# sample.net
KiCad netlist of a schematic drawn in EAGLE
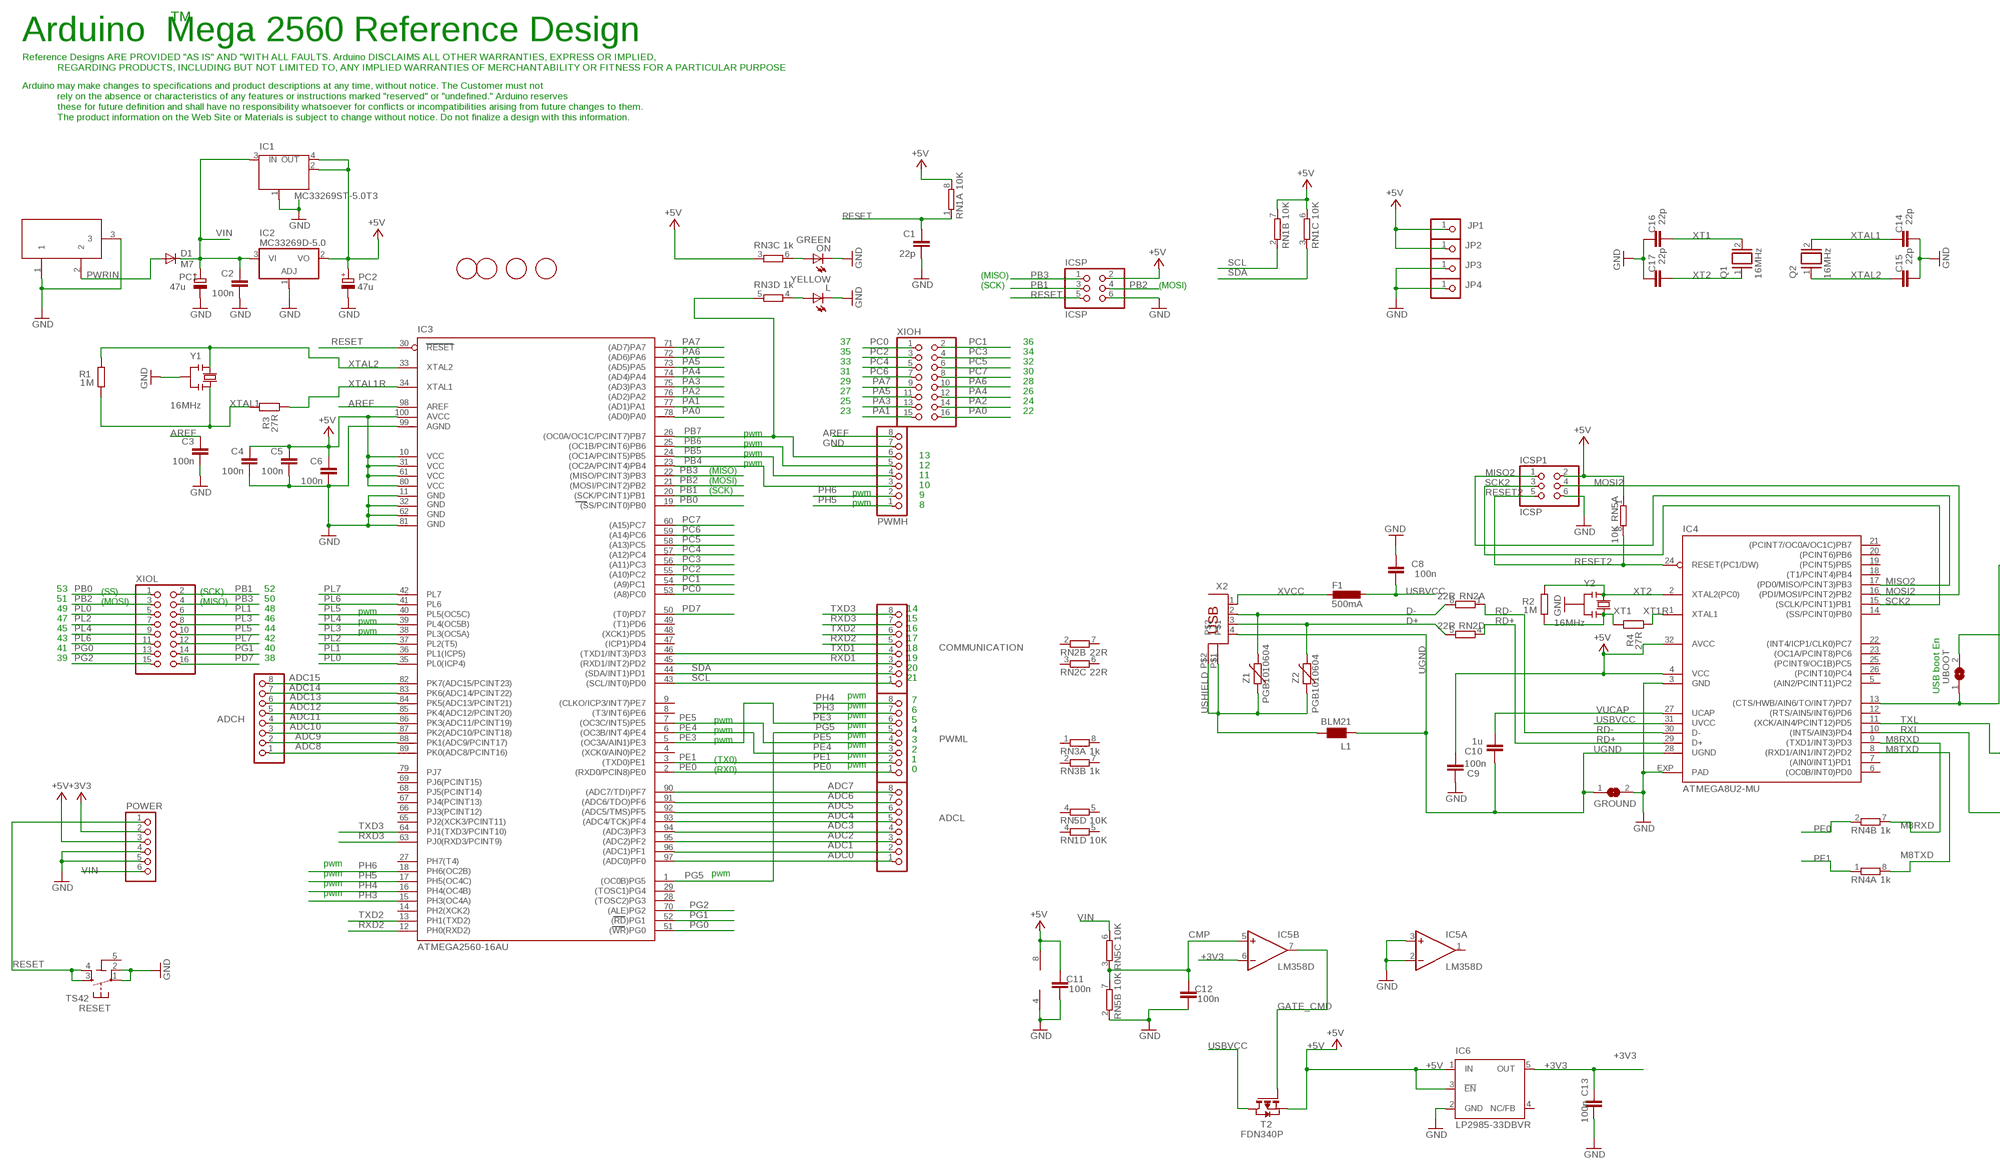
[diagram p0: schematic, sheet 1, part 1 of 2]
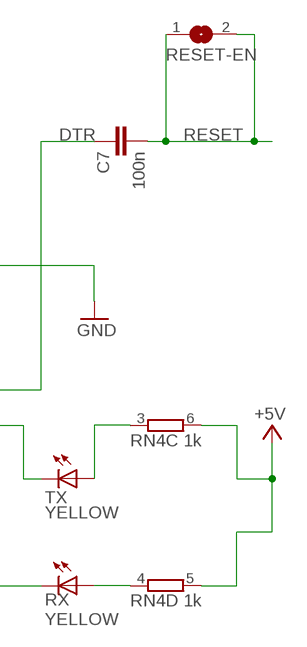
[diagram p1: schematic, sheet 1, part 2 of 2]

(export (version "E")
  (design (tool "Eeschema 10.0.6"))
  (components
    (comp (ref "ADCH")
      (value "PINHD-1X8")
      (footprint "eagle-import:1X08")
      (libsource (lib "eagle-import") (part "PINHD-1X8"))
    )
    (comp (ref "ADCL")
      (value "PINHD-1X8")
      (footprint "eagle-import:1X08")
      (libsource (lib "eagle-import") (part "PINHD-1X8"))
    )
    (comp (ref "C1")
      (value "22p")
      (footprint "eagle-import:C0603-ROUND")
      (libsource (lib "eagle-import") (part "C-EU0603-RND"))
    )
    (comp (ref "C2")
      (value "100n")
      (footprint "eagle-import:C0603-ROUND")
      (libsource (lib "eagle-import") (part "C-EU0603-RND"))
    )
    (comp (ref "C3")
      (value "100n")
      (footprint "eagle-import:C0603-ROUND")
      (libsource (lib "eagle-import") (part "C-EU0603-RND"))
    )
    (comp (ref "C4")
      (value "100n")
      (footprint "eagle-import:C0603-ROUND")
      (libsource (lib "eagle-import") (part "C-EU0603-RND"))
    )
    (comp (ref "C5")
      (value "100n")
      (footprint "eagle-import:C0603-ROUND")
      (libsource (lib "eagle-import") (part "C-EU0603-RND"))
    )
    (comp (ref "C6")
      (value "100n")
      (footprint "eagle-import:C0603-ROUND")
      (libsource (lib "eagle-import") (part "C-EU0603-RND"))
    )
    (comp (ref "C7")
      (value "100n")
      (footprint "eagle-import:C0603-ROUND")
      (libsource (lib "eagle-import") (part "C-EU0603-RND"))
    )
    (comp (ref "C8")
      (value "100n")
      (footprint "eagle-import:C0603")
      (libsource (lib "eagle-import") (part "rcl_C-EUC0603"))
    )
    (comp (ref "C9")
      (value "100n")
      (footprint "eagle-import:C0603-ROUND")
      (libsource (lib "eagle-import") (part "C-EU0603-RND"))
    )
    (comp (ref "C10")
      (value "1u")
      (footprint "eagle-import:C0603-ROUND")
      (libsource (lib "eagle-import") (part "C-EU0603-RND"))
    )
    (comp (ref "C11")
      (value "100n")
      (footprint "eagle-import:C0603")
      (libsource (lib "eagle-import") (part "rcl_C-EUC0603"))
    )
    (comp (ref "C12")
      (value "100n")
      (footprint "eagle-import:C0603-ROUND")
      (libsource (lib "eagle-import") (part "C-EU0603-RND"))
    )
    (comp (ref "C13")
      (value "100n")
      (footprint "eagle-import:C0603-ROUND")
      (libsource (lib "eagle-import") (part "C-EU0603-RND"))
    )
    (comp (ref "C14")
      (value "22p")
      (footprint "eagle-import:C0603-ROUND")
      (libsource (lib "eagle-import") (part "C-EU0603-RND"))
    )
    (comp (ref "C15")
      (value "22p")
      (footprint "eagle-import:C0603-ROUND")
      (libsource (lib "eagle-import") (part "C-EU0603-RND"))
    )
    (comp (ref "C16")
      (value "22p")
      (footprint "eagle-import:C0603-ROUND")
      (libsource (lib "eagle-import") (part "C-EU0603-RND"))
    )
    (comp (ref "C17")
      (value "22p")
      (footprint "eagle-import:C0603-ROUND")
      (libsource (lib "eagle-import") (part "C-EU0603-RND"))
    )
    (comp (ref "COMMUNICATION")
      (value "PINHD-1X8")
      (footprint "eagle-import:1X08")
      (libsource (lib "eagle-import") (part "PINHD-1X8"))
    )
    (comp (ref "D1")
      (value "M7")
      (footprint "eagle-import:SMB")
      (libsource (lib "eagle-import") (part "DIODE-SMB"))
    )
    (comp (ref "F1")
      (value "500mA")
      (footprint "eagle-import:L1812")
      (libsource (lib "eagle-import") (part "L-EUL1812"))
    )
    (comp (ref "GROUND")
      (value "SJ")
      (footprint "eagle-import:SJ")
      (libsource (lib "eagle-import") (part "SJ"))
    )
    (comp (ref "IC1")
      (value "MC33269ST-5.0T3")
      (footprint "eagle-import:SOT223")
      (libsource (lib "eagle-import") (part "MC33269ST-3.3T3"))
    )
    (comp (ref "IC2")
      (value "MC33269D-5.0")
      (footprint "eagle-import:DPACK")
      (libsource (lib "eagle-import") (part "MC33269?D-5.0"))
    )
    (comp (ref "IC3")
      (value "ATMEGA2560-16AU")
      (footprint "eagle-import:TQFP100")
      (libsource (lib "eagle-import") (part "ATMEGAAU1280-16"))
    )
    (comp (ref "IC4")
      (value "ATMEGA8U2-MU")
      (footprint "eagle-import:QFN32")
      (libsource (lib "eagle-import") (part "ATMEGA8U2-MU"))
    )
    (comp (ref "IC5")
      (value "LM358D")
      (footprint "eagle-import:SO08")
      (libsource (lib "eagle-import") (part "LM358D"))
    )
    (comp (ref "IC6")
      (value "LP2985-33DBVR")
      (footprint "eagle-import:SOT23-DBV")
      (libsource (lib "eagle-import") (part "TPS77033"))
    )
    (comp (ref "ICSP")
      (value "ICSP")
      (footprint "eagle-import:2X03")
      (libsource (lib "eagle-import") (part "PINHD-2X3"))
    )
    (comp (ref "ICSP1")
      (value "ICSP")
      (footprint "eagle-import:2X03")
      (libsource (lib "eagle-import") (part "PINHD-2X3"))
    )
    (comp (ref "JP1")
      (value "PINHD-1X1")
      (footprint "eagle-import:1X01")
      (libsource (lib "eagle-import") (part "PINHD-1X1"))
    )
    (comp (ref "JP2")
      (value "PINHD-1X1")
      (footprint "eagle-import:1X01")
      (libsource (lib "eagle-import") (part "PINHD-1X1"))
    )
    (comp (ref "JP3")
      (value "PINHD-1X1")
      (footprint "eagle-import:1X01")
      (libsource (lib "eagle-import") (part "PINHD-1X1"))
    )
    (comp (ref "JP4")
      (value "PINHD-1X1")
      (footprint "eagle-import:1X01")
      (libsource (lib "eagle-import") (part "PINHD-1X1"))
    )
    (comp (ref "L")
      (value "YELLOW")
      (footprint "eagle-import:CHIP-LED0805")
      (libsource (lib "eagle-import") (part "LEDCHIP-LED0805"))
    )
    (comp (ref "L1")
      (value "BLM21")
      (footprint "eagle-import:0805")
      (libsource (lib "eagle-import") (part "WE-CBF_0805"))
    )
    (comp (ref "ON")
      (value "GREEN")
      (footprint "eagle-import:CHIP-LED0805")
      (libsource (lib "eagle-import") (part "LEDCHIP-LED0805"))
    )
    (comp (ref "PC1")
      (value "47u")
      (footprint "eagle-import:PANASONIC_D")
      (libsource (lib "eagle-import") (part "CPOL-EUD"))
    )
    (comp (ref "PC2")
      (value "47u")
      (footprint "eagle-import:PANASONIC_D")
      (libsource (lib "eagle-import") (part "CPOL-EUD"))
    )
    (comp (ref "POWER")
      (value "PINHD-1X6")
      (footprint "eagle-import:1X06")
      (libsource (lib "eagle-import") (part "PINHD-1X6"))
    )
    (comp (ref "PWMH")
      (value "PINHD-1X8")
      (footprint "eagle-import:1X08")
      (libsource (lib "eagle-import") (part "PINHD-1X8"))
    )
    (comp (ref "PWML")
      (value "PINHD-1X8")
      (footprint "eagle-import:1X08")
      (libsource (lib "eagle-import") (part "PINHD-1X8"))
    )
    (comp (ref "Q1")
      (value "16MHz")
      (footprint "eagle-import:QS")
      (libsource (lib "eagle-import") (part "XTAL/S"))
    )
    (comp (ref "Q2")
      (value "16MHz")
      (footprint "eagle-import:QS")
      (libsource (lib "eagle-import") (part "XTAL/S"))
    )
    (comp (ref "R1")
      (value "1M")
      (footprint "eagle-import:R0603-ROUND")
      (libsource (lib "eagle-import") (part "R-EU_R0603"))
    )
    (comp (ref "R2")
      (value "1M")
      (footprint "eagle-import:R0603-ROUND")
      (libsource (lib "eagle-import") (part "R-EU_R0603"))
    )
    (comp (ref "R3")
      (value "27R")
      (footprint "eagle-import:R0603-ROUND")
      (libsource (lib "eagle-import") (part "R-EU_R0603"))
    )
    (comp (ref "R4")
      (value "27R")
      (footprint "eagle-import:R0603-ROUND")
      (libsource (lib "eagle-import") (part "R-EU_R0603"))
    )
    (comp (ref "RESET")
      (value "TS42")
      (footprint "eagle-import:TS42")
      (libsource (lib "eagle-import") (part "TS42"))
    )
    (comp (ref "RESET-EN")
      (value "SJ")
      (footprint "eagle-import:SJ")
      (libsource (lib "eagle-import") (part "SJ"))
    )
    (comp (ref "RN1")
      (value "10K")
      (footprint "eagle-import:CAT16")
      (libsource (lib "eagle-import") (part "4R-NCAT16"))
    )
    (comp (ref "RN2")
      (value "22R")
      (footprint "eagle-import:CAY16")
      (libsource (lib "eagle-import") (part "4R-NCAY16"))
    )
    (comp (ref "RN3")
      (value "1k")
      (footprint "eagle-import:CAY16")
      (libsource (lib "eagle-import") (part "4R-NCAY16"))
    )
    (comp (ref "RN4")
      (value "1k")
      (footprint "eagle-import:CAY16")
      (libsource (lib "eagle-import") (part "4R-NCAY16"))
    )
    (comp (ref "RN5")
      (value "10K")
      (footprint "eagle-import:CAT16")
      (libsource (lib "eagle-import") (part "4R-NCAT16"))
    )
    (comp (ref "RX")
      (value "YELLOW")
      (footprint "eagle-import:CHIP-LED0805")
      (libsource (lib "eagle-import") (part "LEDCHIP-LED0805"))
    )
    (comp (ref "T2")
      (value "FDN340P")
      (footprint "eagle-import:SOT-23")
      (libsource (lib "eagle-import") (part "PMOSSOT23"))
    )
    (comp (ref "TX")
      (value "YELLOW")
      (footprint "eagle-import:CHIP-LED0805")
      (libsource (lib "eagle-import") (part "LEDCHIP-LED0805"))
    )
    (comp (ref "U$2")
      (value "FIDUCIALMOUNT")
      (footprint "eagle-import:FIDUCIA-MOUNT")
      (libsource (lib "eagle-import") (part "FIDUCIALMOUNT"))
    )
    (comp (ref "U$3")
      (value "FIDUCIALMOUNT")
      (footprint "eagle-import:FIDUCIA-MOUNT")
      (libsource (lib "eagle-import") (part "FIDUCIALMOUNT"))
    )
    (comp (ref "U$4")
      (value "FIDUCIALMOUNT")
      (footprint "eagle-import:FIDUCIA-MOUNT")
      (libsource (lib "eagle-import") (part "FIDUCIALMOUNT"))
    )
    (comp (ref "U$5")
      (value "FIDUCIALMOUNT")
      (footprint "eagle-import:FIDUCIA-MOUNT")
      (libsource (lib "eagle-import") (part "FIDUCIALMOUNT"))
    )
    (comp (ref "UBOOT")
      (value "SJ")
      (footprint "eagle-import:SJ")
      (libsource (lib "eagle-import") (part "SJ"))
    )
    (comp (ref "X1")
      (value "DC21MMX")
      (footprint "eagle-import:DC-21MM")
      (libsource (lib "eagle-import") (part "DC21MMX"))
    )
    (comp (ref "X2")
      (value "PN61729")
      (footprint "eagle-import:PN61729")
      (libsource (lib "eagle-import") (part "PN61729"))
    )
    (comp (ref "XIOH")
      (value "PINHD-2X8")
      (footprint "eagle-import:2X08")
      (libsource (lib "eagle-import") (part "PINHD-2X8"))
    )
    (comp (ref "XIOL")
      (value "PINHD-2X8")
      (footprint "eagle-import:2X08")
      (libsource (lib "eagle-import") (part "PINHD-2X8"))
    )
    (comp (ref "Y1")
      (value "16MHz")
      (footprint "eagle-import:RESONATOR")
      (libsource (lib "eagle-import") (part "RESONATORMU"))
    )
    (comp (ref "Y2")
      (value "16MHz")
      (footprint "eagle-import:RESONATOR")
      (libsource (lib "eagle-import") (part "RESONATORMU"))
    )
    (comp (ref "Z1")
      (value "PGB1010604")
      (footprint "eagle-import:CT_CN0603")
      (libsource (lib "eagle-import") (part "VARISTORCN0603"))
    )
    (comp (ref "Z2")
      (value "PGB1010604")
      (footprint "eagle-import:CT_CN0603")
      (libsource (lib "eagle-import") (part "VARISTORCN0603"))
    )
  )
  (nets
    (net (code "1") (name "+3V3") (class "Default")
      (node (ref "C13") (pin "2") (pinfunction "2_2") (pintype "passive"))
      (node (ref "IC5") (pin "6") (pinfunction "-IN_6") (pintype "input"))
      (node (ref "IC6") (pin "5") (pinfunction "OUT_5") (pintype "passive"))
      (node (ref "POWER") (pin "2") (pinfunction "2_2") (pintype "passive"))
    )
    (net (code "2") (name "+5V") (class "Default")
      (node (ref "C11") (pin "2") (pinfunction "2_2") (pintype "passive"))
      (node (ref "C4") (pin "1") (pinfunction "1_1") (pintype "passive"))
      (node (ref "C5") (pin "1") (pinfunction "1_1") (pintype "passive"))
      (node (ref "C6") (pin "1") (pinfunction "1_1") (pintype "passive"))
      (node (ref "C9") (pin "1") (pinfunction "1_1") (pintype "passive"))
      (node (ref "IC1") (pin "2") (pinfunction "OUT_2") (pintype "passive"))
      (node (ref "IC1") (pin "4") (pinfunction "OUT_4") (pintype "passive"))
      (node (ref "IC2") (pin "2") (pinfunction "VO_2") (pintype "passive"))
      (node (ref "IC3") (pin "10") (pinfunction "VCC_10") (pintype "power_in"))
      (node (ref "IC3") (pin "100") (pinfunction "AVCC_100") (pintype "power_in"))
      (node (ref "IC3") (pin "31") (pinfunction "VCC1_31") (pintype "power_in"))
      (node (ref "IC3") (pin "61") (pinfunction "VCC2_61") (pintype "power_in"))
      (node (ref "IC3") (pin "80") (pinfunction "VCC3_80") (pintype "power_in"))
      (node (ref "IC4") (pin "32") (pinfunction "AVCC_32") (pintype "power_in"))
      (node (ref "IC4") (pin "4") (pinfunction "VCC_4") (pintype "power_in"))
      (node (ref "IC5") (pin "8") (pinfunction "V+_8") (pintype "power_in"))
      (node (ref "IC6") (pin "1") (pinfunction "IN_1") (pintype "input"))
      (node (ref "IC6") (pin "3") (pinfunction "~{EN}_3") (pintype "input"))
      (node (ref "ICSP") (pin "2") (pinfunction "2_2") (pintype "passive"))
      (node (ref "ICSP1") (pin "2") (pinfunction "2_2") (pintype "passive"))
      (node (ref "JP1") (pin "1") (pinfunction "1_1") (pintype "passive"))
      (node (ref "JP2") (pin "1") (pinfunction "1_1") (pintype "passive"))
      (node (ref "PC2") (pin "+") (pinfunction "+_+") (pintype "passive"))
      (node (ref "POWER") (pin "3") (pinfunction "3_3") (pintype "passive"))
      (node (ref "RN1") (pin "6") (pinfunction "2_6") (pintype "passive"))
      (node (ref "RN1") (pin "7") (pinfunction "2_7") (pintype "passive"))
      (node (ref "RN1") (pin "8") (pinfunction "2_8") (pintype "passive"))
      (node (ref "RN3") (pin "3") (pinfunction "1_3") (pintype "passive"))
      (node (ref "RN4") (pin "5") (pinfunction "2_5") (pintype "passive"))
      (node (ref "RN4") (pin "6") (pinfunction "2_6") (pintype "passive"))
      (node (ref "RN5") (pin "1") (pinfunction "1_1") (pintype "passive"))
      (node (ref "T2") (pin "2") (pinfunction "S_2") (pintype "passive"))
    )
    (net (code "3") (name "/5-GND") (class "Default")
      (node (ref "RESET") (pin "5") (pinfunction "5-GND_5") (pintype "power_in"))
    )
    (net (code "4") (name "/ADC0") (class "Default")
      (node (ref "ADCL") (pin "1") (pinfunction "1_1") (pintype "passive"))
      (node (ref "IC3") (pin "97") (pinfunction "(ADC0)PF0_97") (pintype "bidirectional"))
    )
    (net (code "5") (name "/ADC1") (class "Default")
      (node (ref "ADCL") (pin "2") (pinfunction "2_2") (pintype "passive"))
      (node (ref "IC3") (pin "96") (pinfunction "(ADC1)PF1_96") (pintype "bidirectional"))
    )
    (net (code "6") (name "/ADC2") (class "Default")
      (node (ref "ADCL") (pin "3") (pinfunction "3_3") (pintype "passive"))
      (node (ref "IC3") (pin "95") (pinfunction "(ADC2)PF2_95") (pintype "bidirectional"))
    )
    (net (code "7") (name "/ADC3") (class "Default")
      (node (ref "ADCL") (pin "4") (pinfunction "4_4") (pintype "passive"))
      (node (ref "IC3") (pin "94") (pinfunction "(ADC3)PF3_94") (pintype "bidirectional"))
    )
    (net (code "8") (name "/ADC4") (class "Default")
      (node (ref "ADCL") (pin "5") (pinfunction "5_5") (pintype "passive"))
      (node (ref "IC3") (pin "93") (pinfunction "(ADC4/TCK)PF4_93") (pintype "bidirectional"))
    )
    (net (code "9") (name "/ADC5") (class "Default")
      (node (ref "ADCL") (pin "6") (pinfunction "6_6") (pintype "passive"))
      (node (ref "IC3") (pin "92") (pinfunction "(ADC5/TMS)PF5_92") (pintype "bidirectional"))
    )
    (net (code "10") (name "/ADC6") (class "Default")
      (node (ref "ADCL") (pin "7") (pinfunction "7_7") (pintype "passive"))
      (node (ref "IC3") (pin "91") (pinfunction "(ADC6/TDO)PF6_91") (pintype "bidirectional"))
    )
    (net (code "11") (name "/ADC7") (class "Default")
      (node (ref "ADCL") (pin "8") (pinfunction "8_8") (pintype "passive"))
      (node (ref "IC3") (pin "90") (pinfunction "(ADC7/TDI)PF7_90") (pintype "bidirectional"))
    )
    (net (code "12") (name "/ADC8") (class "Default")
      (node (ref "ADCH") (pin "1") (pinfunction "1_1") (pintype "passive"))
      (node (ref "IC3") (pin "89") (pinfunction "PK0(ADC8/PCINT16)_89") (pintype "bidirectional"))
    )
    (net (code "13") (name "/ADC9") (class "Default")
      (node (ref "ADCH") (pin "2") (pinfunction "2_2") (pintype "passive"))
      (node (ref "IC3") (pin "88") (pinfunction "PK1(ADC9/PCINT17)_88") (pintype "bidirectional"))
    )
    (net (code "14") (name "/ADC10") (class "Default")
      (node (ref "ADCH") (pin "3") (pinfunction "3_3") (pintype "passive"))
      (node (ref "IC3") (pin "87") (pinfunction "PK2(ADC10/PCINT18)_87") (pintype "bidirectional"))
    )
    (net (code "15") (name "/ADC11") (class "Default")
      (node (ref "ADCH") (pin "4") (pinfunction "4_4") (pintype "passive"))
      (node (ref "IC3") (pin "86") (pinfunction "PK3(ADC11/PCINT19)_86") (pintype "bidirectional"))
    )
    (net (code "16") (name "/ADC12") (class "Default")
      (node (ref "ADCH") (pin "5") (pinfunction "5_5") (pintype "passive"))
      (node (ref "IC3") (pin "85") (pinfunction "PK4(ADC12/PCINT20)_85") (pintype "bidirectional"))
    )
    (net (code "17") (name "/ADC13") (class "Default")
      (node (ref "ADCH") (pin "6") (pinfunction "6_6") (pintype "passive"))
      (node (ref "IC3") (pin "84") (pinfunction "PK5(ADC13/PCINT21)_84") (pintype "bidirectional"))
    )
    (net (code "18") (name "/ADC14") (class "Default")
      (node (ref "ADCH") (pin "7") (pinfunction "7_7") (pintype "passive"))
      (node (ref "IC3") (pin "83") (pinfunction "PK6(ADC14/PCINT22)_83") (pintype "bidirectional"))
    )
    (net (code "19") (name "/ADC15") (class "Default")
      (node (ref "ADCH") (pin "8") (pinfunction "8_8") (pintype "passive"))
      (node (ref "IC3") (pin "82") (pinfunction "PK7(ADC15/PCINT23)_82") (pintype "bidirectional"))
    )
    (net (code "20") (name "/AREF") (class "Default")
      (node (ref "C3") (pin "1") (pinfunction "1_1") (pintype "passive"))
      (node (ref "IC3") (pin "98") (pinfunction "AREF_98") (pintype "bidirectional"))
      (node (ref "PWMH") (pin "8") (pinfunction "8_8") (pintype "passive"))
    )
    (net (code "21") (name "/CMP") (class "Default")
      (node (ref "C12") (pin "2") (pinfunction "2_2") (pintype "passive"))
      (node (ref "IC5") (pin "5") (pinfunction "+IN_5") (pintype "input"))
      (node (ref "RN5") (pin "3") (pinfunction "1_3") (pintype "passive"))
      (node (ref "RN5") (pin "7") (pinfunction "2_7") (pintype "passive"))
    )
    (net (code "22") (name "/D+") (class "Default")
      (node (ref "RN2") (pin "5") (pinfunction "2_5") (pintype "passive"))
      (node (ref "X2") (pin "3") (pinfunction "3_3") (pintype "bidirectional"))
      (node (ref "Z2") (pin "2") (pinfunction "2_2") (pintype "passive"))
    )
    (net (code "23") (name "/D-") (class "Default")
      (node (ref "RN2") (pin "8") (pinfunction "2_8") (pintype "passive"))
      (node (ref "X2") (pin "2") (pinfunction "2_2") (pintype "bidirectional"))
      (node (ref "Z1") (pin "2") (pinfunction "2_2") (pintype "passive"))
    )
    (net (code "24") (name "/DTR") (class "Default")
      (node (ref "C7") (pin "1") (pinfunction "1_1") (pintype "passive"))
      (node (ref "IC4") (pin "13") (pinfunction "(CTS/HWB/AIN6/TO/INT7)PD7_13") (pintype "bidirectional"))
      (node (ref "UBOOT") (pin "1") (pinfunction "1_1") (pintype "passive"))
    )
    (net (code "25") (name "/GATE_CMD") (class "Default")
      (node (ref "IC5") (pin "7") (pinfunction "OUT_7") (pintype "output"))
      (node (ref "T2") (pin "3") (pinfunction "G_3") (pintype "passive"))
    )
    (net (code "26") (name "/M8RXD") (class "Default")
      (node (ref "IC4") (pin "9") (pinfunction "(TXD1/INT3)PD3_9") (pintype "bidirectional"))
      (node (ref "RN4") (pin "7") (pinfunction "2_7") (pintype "passive"))
    )
    (net (code "27") (name "/M8TXD") (class "Default")
      (node (ref "IC4") (pin "8") (pinfunction "(RXD1/AIN1/INT2)PD2_8") (pintype "bidirectional"))
      (node (ref "RN4") (pin "8") (pinfunction "2_8") (pintype "passive"))
    )
    (net (code "28") (name "/MISO2") (class "Default")
      (node (ref "IC4") (pin "17") (pinfunction "(PD0/MISO/PCINT3)PB3_17") (pintype "bidirectional"))
      (node (ref "ICSP1") (pin "1") (pinfunction "1_1") (pintype "passive"))
    )
    (net (code "29") (name "/MOSI2") (class "Default")
      (node (ref "IC4") (pin "16") (pinfunction "(PDI/MOSI/PCINT2)PB2_16") (pintype "bidirectional"))
      (node (ref "ICSP1") (pin "4") (pinfunction "4_4") (pintype "passive"))
    )
    (net (code "30") (name "/PA0") (class "Default")
      (node (ref "IC3") (pin "78") (pinfunction "(AD0)PA0_78") (pintype "bidirectional"))
      (node (ref "XIOH") (pin "16") (pinfunction "16_16") (pintype "passive"))
    )
    (net (code "31") (name "/PA1") (class "Default")
      (node (ref "IC3") (pin "77") (pinfunction "(AD1)PA1_77") (pintype "bidirectional"))
      (node (ref "XIOH") (pin "15") (pinfunction "15_15") (pintype "passive"))
    )
    (net (code "32") (name "/PA2") (class "Default")
      (node (ref "IC3") (pin "76") (pinfunction "(AD2)PA2_76") (pintype "bidirectional"))
      (node (ref "XIOH") (pin "14") (pinfunction "14_14") (pintype "passive"))
    )
    (net (code "33") (name "/PA3") (class "Default")
      (node (ref "IC3") (pin "75") (pinfunction "(AD3)PA3_75") (pintype "bidirectional"))
      (node (ref "XIOH") (pin "13") (pinfunction "13_13") (pintype "passive"))
    )
    (net (code "34") (name "/PA4") (class "Default")
      (node (ref "IC3") (pin "74") (pinfunction "(AD4)PA4_74") (pintype "bidirectional"))
      (node (ref "XIOH") (pin "12") (pinfunction "12_12") (pintype "passive"))
    )
    (net (code "35") (name "/PA5") (class "Default")
      (node (ref "IC3") (pin "73") (pinfunction "(AD5)PA5_73") (pintype "bidirectional"))
      (node (ref "XIOH") (pin "11") (pinfunction "11_11") (pintype "passive"))
    )
    (net (code "36") (name "/PA6") (class "Default")
      (node (ref "IC3") (pin "72") (pinfunction "(AD6)PA6_72") (pintype "bidirectional"))
      (node (ref "XIOH") (pin "10") (pinfunction "10_10") (pintype "passive"))
    )
    (net (code "37") (name "/PA7") (class "Default")
      (node (ref "IC3") (pin "71") (pinfunction "(AD7)PA7_71") (pintype "bidirectional"))
      (node (ref "XIOH") (pin "9") (pinfunction "9_9") (pintype "passive"))
    )
    (net (code "38") (name "/PB0") (class "Default")
      (node (ref "IC3") (pin "19") (pinfunction "(SS/PCINT0)PB0_19") (pintype "bidirectional"))
      (node (ref "XIOL") (pin "1") (pinfunction "1_1") (pintype "passive"))
    )
    (net (code "39") (name "/PB1") (class "Default")
      (node (ref "IC3") (pin "20") (pinfunction "(SCK/PCINT1)PB1_20") (pintype "bidirectional"))
      (node (ref "ICSP") (pin "3") (pinfunction "3_3") (pintype "passive"))
      (node (ref "XIOL") (pin "2") (pinfunction "2_2") (pintype "passive"))
    )
    (net (code "40") (name "/PB2") (class "Default")
      (node (ref "IC3") (pin "21") (pinfunction "(MOSI/PCINT2)PB2_21") (pintype "bidirectional"))
      (node (ref "ICSP") (pin "4") (pinfunction "4_4") (pintype "passive"))
      (node (ref "XIOL") (pin "3") (pinfunction "3_3") (pintype "passive"))
    )
    (net (code "41") (name "/PB3") (class "Default")
      (node (ref "IC3") (pin "22") (pinfunction "(MISO/PCINT3)PB3_22") (pintype "bidirectional"))
      (node (ref "ICSP") (pin "1") (pinfunction "1_1") (pintype "passive"))
      (node (ref "XIOL") (pin "4") (pinfunction "4_4") (pintype "passive"))
    )
    (net (code "42") (name "/PB4") (class "Default")
      (node (ref "IC3") (pin "23") (pinfunction "(OC2A/PCINT4)PB4_23") (pintype "bidirectional"))
      (node (ref "PWMH") (pin "3") (pinfunction "3_3") (pintype "passive"))
    )
    (net (code "43") (name "/PB5") (class "Default")
      (node (ref "IC3") (pin "24") (pinfunction "(OC1A/PCINT5)PB5_24") (pintype "bidirectional"))
      (node (ref "PWMH") (pin "4") (pinfunction "4_4") (pintype "passive"))
    )
    (net (code "44") (name "/PB6") (class "Default")
      (node (ref "IC3") (pin "25") (pinfunction "(OC1B/PCINT6)PB6_25") (pintype "bidirectional"))
      (node (ref "PWMH") (pin "5") (pinfunction "5_5") (pintype "passive"))
    )
    (net (code "45") (name "/PB7") (class "Default")
      (node (ref "IC3") (pin "26") (pinfunction "(OC0A/OC1C/PCINT7)PB7_26") (pintype "bidirectional"))
      (node (ref "PWMH") (pin "6") (pinfunction "6_6") (pintype "passive"))
      (node (ref "RN3") (pin "5") (pinfunction "2_5") (pintype "passive"))
    )
    (net (code "46") (name "/PC0") (class "Default")
      (node (ref "IC3") (pin "53") (pinfunction "(A8)PC0_53") (pintype "bidirectional"))
      (node (ref "XIOH") (pin "1") (pinfunction "1_1") (pintype "passive"))
    )
    (net (code "47") (name "/PC1") (class "Default")
      (node (ref "IC3") (pin "54") (pinfunction "(A9)PC1_54") (pintype "bidirectional"))
      (node (ref "XIOH") (pin "2") (pinfunction "2_2") (pintype "passive"))
    )
    (net (code "48") (name "/PC2") (class "Default")
      (node (ref "IC3") (pin "55") (pinfunction "(A10)PC2_55") (pintype "bidirectional"))
      (node (ref "XIOH") (pin "3") (pinfunction "3_3") (pintype "passive"))
    )
    (net (code "49") (name "/PC3") (class "Default")
      (node (ref "IC3") (pin "56") (pinfunction "(A11)PC3_56") (pintype "bidirectional"))
      (node (ref "XIOH") (pin "4") (pinfunction "4_4") (pintype "passive"))
    )
    (net (code "50") (name "/PC4") (class "Default")
      (node (ref "IC3") (pin "57") (pinfunction "(A12)PC4_57") (pintype "bidirectional"))
      (node (ref "XIOH") (pin "5") (pinfunction "5_5") (pintype "passive"))
    )
    (net (code "51") (name "/PC5") (class "Default")
      (node (ref "IC3") (pin "58") (pinfunction "(A13)PC5_58") (pintype "bidirectional"))
      (node (ref "XIOH") (pin "6") (pinfunction "6_6") (pintype "passive"))
    )
    (net (code "52") (name "/PC6") (class "Default")
      (node (ref "IC3") (pin "59") (pinfunction "(A14)PC6_59") (pintype "bidirectional"))
      (node (ref "XIOH") (pin "7") (pinfunction "7_7") (pintype "passive"))
    )
    (net (code "53") (name "/PC7") (class "Default")
      (node (ref "IC3") (pin "60") (pinfunction "(A15)PC7_60") (pintype "bidirectional"))
      (node (ref "XIOH") (pin "8") (pinfunction "8_8") (pintype "passive"))
    )
    (net (code "54") (name "/PD7") (class "Default")
      (node (ref "IC3") (pin "50") (pinfunction "(T0)PD7_50") (pintype "bidirectional"))
      (node (ref "XIOL") (pin "16") (pinfunction "16_16") (pintype "passive"))
    )
    (net (code "55") (name "/PE0") (class "Default")
      (node (ref "IC3") (pin "2") (pinfunction "(RXD0/PCIN8)PE0_2") (pintype "bidirectional"))
      (node (ref "PWML") (pin "1") (pinfunction "1_1") (pintype "passive"))
      (node (ref "RN4") (pin "2") (pinfunction "1_2") (pintype "passive"))
    )
    (net (code "56") (name "/PE1") (class "Default")
      (node (ref "IC3") (pin "3") (pinfunction "(TXD0)PE1_3") (pintype "bidirectional"))
      (node (ref "PWML") (pin "2") (pinfunction "2_2") (pintype "passive"))
      (node (ref "RN4") (pin "1") (pinfunction "1_1") (pintype "passive"))
    )
    (net (code "57") (name "/PE3") (class "Default")
      (node (ref "IC3") (pin "5") (pinfunction "(OC3A/AIN1)PE3_5") (pintype "bidirectional"))
      (node (ref "PWML") (pin "6") (pinfunction "6_6") (pintype "passive"))
    )
    (net (code "58") (name "/PE4") (class "Default")
      (node (ref "IC3") (pin "6") (pinfunction "(OC3B/INT4)PE4_6") (pintype "bidirectional"))
      (node (ref "PWML") (pin "3") (pinfunction "3_3") (pintype "passive"))
    )
    (net (code "59") (name "/PE5") (class "Default")
      (node (ref "IC3") (pin "7") (pinfunction "(OC3C/INT5)PE5_7") (pintype "bidirectional"))
      (node (ref "PWML") (pin "4") (pinfunction "4_4") (pintype "passive"))
    )
    (net (code "60") (name "/PG0") (class "Default")
      (node (ref "IC3") (pin "51") (pinfunction "(WR)PG0_51") (pintype "bidirectional"))
      (node (ref "XIOL") (pin "13") (pinfunction "13_13") (pintype "passive"))
    )
    (net (code "61") (name "/PG1") (class "Default")
      (node (ref "IC3") (pin "52") (pinfunction "(RD)PG1_52") (pintype "bidirectional"))
      (node (ref "XIOL") (pin "14") (pinfunction "14_14") (pintype "passive"))
    )
    (net (code "62") (name "/PG2") (class "Default")
      (node (ref "IC3") (pin "70") (pinfunction "(ALE)PG2_70") (pintype "bidirectional"))
      (node (ref "XIOL") (pin "15") (pinfunction "15_15") (pintype "passive"))
    )
    (net (code "63") (name "/PG5") (class "Default")
      (node (ref "IC3") (pin "1") (pinfunction "(OC0B)PG5_1") (pintype "bidirectional"))
      (node (ref "PWML") (pin "5") (pinfunction "5_5") (pintype "passive"))
    )
    (net (code "64") (name "/PH3") (class "Default")
      (node (ref "IC3") (pin "15") (pinfunction "PH3(OC4A)_15") (pintype "bidirectional"))
      (node (ref "PWML") (pin "7") (pinfunction "7_7") (pintype "passive"))
    )
    (net (code "65") (name "/PH4") (class "Default")
      (node (ref "IC3") (pin "16") (pinfunction "PH4(OC4B)_16") (pintype "bidirectional"))
      (node (ref "PWML") (pin "8") (pinfunction "8_8") (pintype "passive"))
    )
    (net (code "66") (name "/PH5") (class "Default")
      (node (ref "IC3") (pin "17") (pinfunction "PH5(OC4C)_17") (pintype "bidirectional"))
      (node (ref "PWMH") (pin "1") (pinfunction "1_1") (pintype "passive"))
    )
    (net (code "67") (name "/PH6") (class "Default")
      (node (ref "IC3") (pin "18") (pinfunction "PH6(OC2B)_18") (pintype "bidirectional"))
      (node (ref "PWMH") (pin "2") (pinfunction "2_2") (pintype "passive"))
    )
    (net (code "68") (name "/PL0") (class "Default")
      (node (ref "IC3") (pin "35") (pinfunction "PL0(ICP4)_35") (pintype "bidirectional"))
      (node (ref "XIOL") (pin "5") (pinfunction "5_5") (pintype "passive"))
    )
    (net (code "69") (name "/PL1") (class "Default")
      (node (ref "IC3") (pin "36") (pinfunction "PL1(ICP5)_36") (pintype "bidirectional"))
      (node (ref "XIOL") (pin "6") (pinfunction "6_6") (pintype "passive"))
    )
    (net (code "70") (name "/PL2") (class "Default")
      (node (ref "IC3") (pin "37") (pinfunction "PL2(T5)_37") (pintype "bidirectional"))
      (node (ref "XIOL") (pin "7") (pinfunction "7_7") (pintype "passive"))
    )
    (net (code "71") (name "/PL3") (class "Default")
      (node (ref "IC3") (pin "38") (pinfunction "PL3(OC5A)_38") (pintype "bidirectional"))
      (node (ref "XIOL") (pin "8") (pinfunction "8_8") (pintype "passive"))
    )
    (net (code "72") (name "/PL4") (class "Default")
      (node (ref "IC3") (pin "39") (pinfunction "PL4(OC5B)_39") (pintype "bidirectional"))
      (node (ref "XIOL") (pin "9") (pinfunction "9_9") (pintype "passive"))
    )
    (net (code "73") (name "/PL5") (class "Default")
      (node (ref "IC3") (pin "40") (pinfunction "PL5(OC5C)_40") (pintype "bidirectional"))
      (node (ref "XIOL") (pin "10") (pinfunction "10_10") (pintype "passive"))
    )
    (net (code "74") (name "/PL6") (class "Default")
      (node (ref "IC3") (pin "41") (pinfunction "PL6_41") (pintype "bidirectional"))
      (node (ref "XIOL") (pin "11") (pinfunction "11_11") (pintype "passive"))
    )
    (net (code "75") (name "/PL7") (class "Default")
      (node (ref "IC3") (pin "42") (pinfunction "PL7_42") (pintype "bidirectional"))
      (node (ref "XIOL") (pin "12") (pinfunction "12_12") (pintype "passive"))
    )
    (net (code "76") (name "/PWRIN") (class "Default")
      (node (ref "D1") (pin "A") (pinfunction "A_A") (pintype "passive"))
      (node (ref "X1") (pin "2") (pinfunction "2_2") (pintype "power_in"))
    )
    (net (code "77") (name "/RD+") (class "Default")
      (node (ref "IC4") (pin "29") (pinfunction "D+_29") (pintype "bidirectional"))
      (node (ref "RN2") (pin "4") (pinfunction "1_4") (pintype "passive"))
    )
    (net (code "78") (name "/RD-") (class "Default")
      (node (ref "IC4") (pin "30") (pinfunction "D-_30") (pintype "bidirectional"))
      (node (ref "RN2") (pin "1") (pinfunction "1_1") (pintype "passive"))
    )
    (net (code "79") (name "/RESET") (class "Default")
      (node (ref "C1") (pin "1") (pinfunction "1_1") (pintype "passive"))
      (node (ref "C7") (pin "2") (pinfunction "2_2") (pintype "passive"))
      (node (ref "IC3") (pin "30") (pinfunction "RESET_30") (pintype "input"))
      (node (ref "ICSP") (pin "5") (pinfunction "5_5") (pintype "passive"))
      (node (ref "POWER") (pin "1") (pinfunction "1_1") (pintype "passive"))
      (node (ref "RESET") (pin "3") (pinfunction "3_3") (pintype "passive"))
      (node (ref "RESET") (pin "4") (pinfunction "4_4") (pintype "passive"))
      (node (ref "RESET-EN") (pin "1") (pinfunction "1_1") (pintype "passive"))
      (node (ref "RESET-EN") (pin "2") (pinfunction "2_2") (pintype "passive"))
      (node (ref "RN1") (pin "1") (pinfunction "1_1") (pintype "passive"))
    )
    (net (code "80") (name "/RESET2") (class "Default")
      (node (ref "IC4") (pin "24") (pinfunction "RESET(PC1/DW)_24") (pintype "input"))
      (node (ref "ICSP1") (pin "5") (pinfunction "5_5") (pintype "passive"))
      (node (ref "RN5") (pin "8") (pinfunction "2_8") (pintype "passive"))
    )
    (net (code "81") (name "/RXD1") (class "Default")
      (node (ref "COMMUNICATION") (pin "3") (pinfunction "3_3") (pintype "passive"))
      (node (ref "IC3") (pin "45") (pinfunction "(RXD1/INT2)PD2_45") (pintype "bidirectional"))
    )
    (net (code "82") (name "/RXD2") (class "Default")
      (node (ref "COMMUNICATION") (pin "5") (pinfunction "5_5") (pintype "passive"))
      (node (ref "IC3") (pin "12") (pinfunction "PH0(RXD2)_12") (pintype "bidirectional"))
    )
    (net (code "83") (name "/RXD3") (class "Default")
      (node (ref "COMMUNICATION") (pin "7") (pinfunction "7_7") (pintype "passive"))
      (node (ref "IC3") (pin "63") (pinfunction "PJ0(RXD3/PCINT9)_63") (pintype "bidirectional"))
    )
    (net (code "84") (name "/RXL") (class "Default")
      (node (ref "IC4") (pin "10") (pinfunction "(INT5/AIN3)PD4_10") (pintype "bidirectional"))
      (node (ref "RX") (pin "C") (pinfunction "C_C") (pintype "passive"))
    )
    (net (code "85") (name "/SCK2") (class "Default")
      (node (ref "IC4") (pin "15") (pinfunction "(SCLK/PCINT1)PB1_15") (pintype "bidirectional"))
      (node (ref "ICSP1") (pin "3") (pinfunction "3_3") (pintype "passive"))
    )
    (net (code "86") (name "/SCL") (class "Default")
      (node (ref "COMMUNICATION") (pin "1") (pinfunction "1_1") (pintype "passive"))
      (node (ref "IC3") (pin "43") (pinfunction "(SCL/INT0)PD0_43") (pintype "bidirectional"))
      (node (ref "RN1") (pin "2") (pinfunction "1_2") (pintype "passive"))
    )
    (net (code "87") (name "/SDA") (class "Default")
      (node (ref "COMMUNICATION") (pin "2") (pinfunction "2_2") (pintype "passive"))
      (node (ref "IC3") (pin "44") (pinfunction "(SDA/INT1)PD1_44") (pintype "bidirectional"))
      (node (ref "RN1") (pin "3") (pinfunction "1_3") (pintype "passive"))
    )
    (net (code "88") (name "/TXD1") (class "Default")
      (node (ref "COMMUNICATION") (pin "4") (pinfunction "4_4") (pintype "passive"))
      (node (ref "IC3") (pin "46") (pinfunction "(TXD1/INT3)PD3_46") (pintype "bidirectional"))
    )
    (net (code "89") (name "/TXD2") (class "Default")
      (node (ref "COMMUNICATION") (pin "6") (pinfunction "6_6") (pintype "passive"))
      (node (ref "IC3") (pin "13") (pinfunction "PH1(TXD2)_13") (pintype "bidirectional"))
    )
    (net (code "90") (name "/TXD3") (class "Default")
      (node (ref "COMMUNICATION") (pin "8") (pinfunction "8_8") (pintype "passive"))
      (node (ref "IC3") (pin "64") (pinfunction "PJ1(TXD3/PCINT10)_64") (pintype "bidirectional"))
    )
    (net (code "91") (name "/TXL") (class "Default")
      (node (ref "IC4") (pin "11") (pinfunction "(XCK/AIN4/PCINT12)PD5_11") (pintype "bidirectional"))
      (node (ref "TX") (pin "C") (pinfunction "C_C") (pintype "passive"))
    )
    (net (code "92") (name "/UGND") (class "Default")
      (node (ref "C10") (pin "2") (pinfunction "2_2") (pintype "passive"))
      (node (ref "GROUND") (pin "1") (pinfunction "1_1") (pintype "passive"))
      (node (ref "IC4") (pin "28") (pinfunction "UGND_28") (pintype "power_in"))
      (node (ref "L1") (pin "1") (pinfunction "1_1") (pintype "passive"))
      (node (ref "X2") (pin "4") (pinfunction "4_4") (pintype "bidirectional"))
    )
    (net (code "93") (name "/USBVCC") (class "Default")
      (node (ref "C8") (pin "1") (pinfunction "1_1") (pintype "passive"))
      (node (ref "F1") (pin "1") (pinfunction "1_1") (pintype "passive"))
      (node (ref "IC4") (pin "31") (pinfunction "UVCC_31") (pintype "power_in"))
      (node (ref "T2") (pin "1") (pinfunction "D_1") (pintype "passive"))
    )
    (net (code "94") (name "/USHIELD") (class "Default")
      (node (ref "L1") (pin "2") (pinfunction "2_2") (pintype "passive"))
      (node (ref "X2") (pin "P$1") (pinfunction "P$1_P$1") (pintype "bidirectional"))
      (node (ref "X2") (pin "P$2") (pinfunction "P$2_P$2") (pintype "bidirectional"))
      (node (ref "Z1") (pin "1") (pinfunction "1_1") (pintype "passive"))
      (node (ref "Z2") (pin "1") (pinfunction "1_1") (pintype "passive"))
    )
    (net (code "95") (name "/VIN") (class "Default")
      (node (ref "C2") (pin "1") (pinfunction "1_1") (pintype "passive"))
      (node (ref "D1") (pin "C") (pinfunction "C_C") (pintype "passive"))
      (node (ref "IC1") (pin "3") (pinfunction "IN_3") (pintype "input"))
      (node (ref "IC2") (pin "3") (pinfunction "VI_3") (pintype "input"))
      (node (ref "PC1") (pin "+") (pinfunction "+_+") (pintype "passive"))
      (node (ref "POWER") (pin "6") (pinfunction "6_6") (pintype "passive"))
      (node (ref "RN5") (pin "6") (pinfunction "2_6") (pintype "passive"))
    )
    (net (code "96") (name "/VUCAP") (class "Default")
      (node (ref "C10") (pin "1") (pinfunction "1_1") (pintype "passive"))
      (node (ref "IC4") (pin "27") (pinfunction "UCAP_27") (pintype "passive"))
    )
    (net (code "97") (name "/XT1") (class "Default")
      (node (ref "C16") (pin "1") (pinfunction "1_1") (pintype "passive"))
      (node (ref "Q1") (pin "2") (pinfunction "2_2") (pintype "passive"))
      (node (ref "R2") (pin "1") (pinfunction "1_1") (pintype "passive"))
      (node (ref "R4") (pin "2") (pinfunction "2_2") (pintype "passive"))
      (node (ref "Y2") (pin "3") (pinfunction "3_3") (pintype "passive"))
    )
    (net (code "98") (name "/XT1R") (class "Default")
      (node (ref "IC4") (pin "1") (pinfunction "XTAL1_1") (pintype "bidirectional"))
      (node (ref "R4") (pin "1") (pinfunction "1_1") (pintype "passive"))
    )
    (net (code "99") (name "/XT2") (class "Default")
      (node (ref "C17") (pin "1") (pinfunction "1_1") (pintype "passive"))
      (node (ref "IC4") (pin "2") (pinfunction "XTAL2(PC0)_2") (pintype "bidirectional"))
      (node (ref "Q1") (pin "1") (pinfunction "1_1") (pintype "passive"))
      (node (ref "R2") (pin "2") (pinfunction "2_2") (pintype "passive"))
      (node (ref "Y2") (pin "1") (pinfunction "1_1") (pintype "passive"))
    )
    (net (code "100") (name "/XTAL1") (class "Default")
      (node (ref "C14") (pin "2") (pinfunction "2_2") (pintype "passive"))
      (node (ref "Q2") (pin "2") (pinfunction "2_2") (pintype "passive"))
      (node (ref "R1") (pin "1") (pinfunction "1_1") (pintype "passive"))
      (node (ref "R3") (pin "2") (pinfunction "2_2") (pintype "passive"))
      (node (ref "Y1") (pin "3") (pinfunction "3_3") (pintype "passive"))
    )
    (net (code "101") (name "/XTAL1R") (class "Default")
      (node (ref "IC3") (pin "34") (pinfunction "XTAL1_34") (pintype "input"))
      (node (ref "R3") (pin "1") (pinfunction "1_1") (pintype "passive"))
    )
    (net (code "102") (name "/XTAL2") (class "Default")
      (node (ref "C15") (pin "2") (pinfunction "2_2") (pintype "passive"))
      (node (ref "IC3") (pin "33") (pinfunction "XTAL2_33") (pintype "output"))
      (node (ref "Q2") (pin "1") (pinfunction "1_1") (pintype "passive"))
      (node (ref "R1") (pin "2") (pinfunction "2_2") (pintype "passive"))
      (node (ref "Y1") (pin "1") (pinfunction "1_1") (pintype "passive"))
    )
    (net (code "103") (name "/XVCC") (class "Default")
      (node (ref "F1") (pin "2") (pinfunction "2_2") (pintype "passive"))
      (node (ref "X2") (pin "1") (pinfunction "1_1") (pintype "bidirectional"))
    )
    (net (code "104") (name "GND") (class "Default")
      (node (ref "C1") (pin "2") (pinfunction "2_2") (pintype "passive"))
      (node (ref "C11") (pin "1") (pinfunction "1_1") (pintype "passive"))
      (node (ref "C12") (pin "1") (pinfunction "1_1") (pintype "passive"))
      (node (ref "C13") (pin "1") (pinfunction "1_1") (pintype "passive"))
      (node (ref "C14") (pin "1") (pinfunction "1_1") (pintype "passive"))
      (node (ref "C15") (pin "1") (pinfunction "1_1") (pintype "passive"))
      (node (ref "C16") (pin "2") (pinfunction "2_2") (pintype "passive"))
      (node (ref "C17") (pin "2") (pinfunction "2_2") (pintype "passive"))
      (node (ref "C2") (pin "2") (pinfunction "2_2") (pintype "passive"))
      (node (ref "C3") (pin "2") (pinfunction "2_2") (pintype "passive"))
      (node (ref "C4") (pin "2") (pinfunction "2_2") (pintype "passive"))
      (node (ref "C5") (pin "2") (pinfunction "2_2") (pintype "passive"))
      (node (ref "C6") (pin "2") (pinfunction "2_2") (pintype "passive"))
      (node (ref "C8") (pin "2") (pinfunction "2_2") (pintype "passive"))
      (node (ref "C9") (pin "2") (pinfunction "2_2") (pintype "passive"))
      (node (ref "GROUND") (pin "2") (pinfunction "2_2") (pintype "passive"))
      (node (ref "IC1") (pin "1") (pinfunction "GND/ADJ_1") (pintype "input"))
      (node (ref "IC2") (pin "1") (pinfunction "ADJ_1") (pintype "input"))
      (node (ref "IC3") (pin "11") (pinfunction "GND_11") (pintype "power_in"))
      (node (ref "IC3") (pin "32") (pinfunction "GND1_32") (pintype "power_in"))
      (node (ref "IC3") (pin "62") (pinfunction "GND2_62") (pintype "power_in"))
      (node (ref "IC3") (pin "81") (pinfunction "GND3_81") (pintype "power_in"))
      (node (ref "IC3") (pin "99") (pinfunction "AGND_99") (pintype "power_in"))
      (node (ref "IC4") (pin "3") (pinfunction "GND_3") (pintype "power_in"))
      (node (ref "IC4") (pin "EXP") (pinfunction "PAD_EXP") (pintype "power_in"))
      (node (ref "IC5") (pin "2") (pinfunction "-IN_2") (pintype "input"))
      (node (ref "IC5") (pin "3") (pinfunction "+IN_3") (pintype "input"))
      (node (ref "IC5") (pin "4") (pinfunction "V-_4") (pintype "power_in"))
      (node (ref "IC6") (pin "2") (pinfunction "GND_2") (pintype "power_in"))
      (node (ref "ICSP") (pin "6") (pinfunction "6_6") (pintype "passive"))
      (node (ref "ICSP1") (pin "6") (pinfunction "6_6") (pintype "passive"))
      (node (ref "JP3") (pin "1") (pinfunction "1_1") (pintype "passive"))
      (node (ref "JP4") (pin "1") (pinfunction "1_1") (pintype "passive"))
      (node (ref "L") (pin "C") (pinfunction "C_C") (pintype "passive"))
      (node (ref "ON") (pin "C") (pinfunction "C_C") (pintype "passive"))
      (node (ref "PC1") (pin "-") (pinfunction "-_-") (pintype "passive"))
      (node (ref "PC2") (pin "-") (pinfunction "-_-") (pintype "passive"))
      (node (ref "POWER") (pin "4") (pinfunction "4_4") (pintype "passive"))
      (node (ref "POWER") (pin "5") (pinfunction "5_5") (pintype "passive"))
      (node (ref "PWMH") (pin "7") (pinfunction "7_7") (pintype "passive"))
      (node (ref "RESET") (pin "1") (pinfunction "1_1") (pintype "passive"))
      (node (ref "RESET") (pin "2") (pinfunction "2_2") (pintype "passive"))
      (node (ref "RN5") (pin "2") (pinfunction "1_2") (pintype "passive"))
      (node (ref "UBOOT") (pin "2") (pinfunction "2_2") (pintype "passive"))
      (node (ref "X1") (pin "1") (pinfunction "1_1") (pintype "power_in"))
      (node (ref "X1") (pin "3") (pinfunction "3_3") (pintype "power_in"))
      (node (ref "Y1") (pin "2") (pinfunction "2_2") (pintype "passive"))
      (node (ref "Y2") (pin "2") (pinfunction "2_2") (pintype "passive"))
    )
    (net (code "105") (name "Net-(RN3C-2)") (class "Default")
      (node (ref "ON") (pin "A") (pinfunction "A_A") (pintype "passive"))
      (node (ref "RN3") (pin "6") (pinfunction "2_6") (pintype "passive"))
    )
    (net (code "106") (name "Net-(RN3D-1)") (class "Default")
      (node (ref "L") (pin "A") (pinfunction "A_A") (pintype "passive"))
      (node (ref "RN3") (pin "4") (pinfunction "1_4") (pintype "passive"))
    )
    (net (code "107") (name "Net-(RN4C-1)") (class "Default")
      (node (ref "RN4") (pin "3") (pinfunction "1_3") (pintype "passive"))
      (node (ref "TX") (pin "A") (pinfunction "A_A") (pintype "passive"))
    )
    (net (code "108") (name "Net-(RN4D-1)") (class "Default")
      (node (ref "RN4") (pin "4") (pinfunction "1_4") (pintype "passive"))
      (node (ref "RX") (pin "A") (pinfunction "A_A") (pintype "passive"))
    )
    (net (code "109") (name "unconnected-(IC3-(CLKO{slash}ICP3{slash}INT7)PE7-Pad9)") (class "Default")
      (node (ref "IC3") (pin "9") (pinfunction "(CLKO/ICP3/INT7)PE7_9") (pintype "bidirectional"))
    )
    (net (code "110") (name "unconnected-(IC3-(ICP1)PD4-Pad47)") (class "Default")
      (node (ref "IC3") (pin "47") (pinfunction "(ICP1)PD4_47") (pintype "bidirectional"))
    )
    (net (code "111") (name "unconnected-(IC3-(T1)PD6-Pad49)") (class "Default")
      (node (ref "IC3") (pin "49") (pinfunction "(T1)PD6_49") (pintype "bidirectional"))
    )
    (net (code "112") (name "unconnected-(IC3-(T3{slash}INT6)PE6-Pad8)") (class "Default")
      (node (ref "IC3") (pin "8") (pinfunction "(T3/INT6)PE6_8") (pintype "bidirectional"))
    )
    (net (code "113") (name "unconnected-(IC3-(TOSC1)PG4-Pad29)") (class "Default")
      (node (ref "IC3") (pin "29") (pinfunction "(TOSC1)PG4_29") (pintype "bidirectional"))
    )
    (net (code "114") (name "unconnected-(IC3-(TOSC2)PG3-Pad28)") (class "Default")
      (node (ref "IC3") (pin "28") (pinfunction "(TOSC2)PG3_28") (pintype "bidirectional"))
    )
    (net (code "115") (name "unconnected-(IC3-(XCK0{slash}AIN0)PE2-Pad4)") (class "Default")
      (node (ref "IC3") (pin "4") (pinfunction "(XCK0/AIN0)PE2_4") (pintype "bidirectional"))
    )
    (net (code "116") (name "unconnected-(IC3-(XCK1)PD5-Pad48)") (class "Default")
      (node (ref "IC3") (pin "48") (pinfunction "(XCK1)PD5_48") (pintype "bidirectional"))
    )
    (net (code "117") (name "unconnected-(IC3-PH2(XCK2)-Pad14)") (class "Default")
      (node (ref "IC3") (pin "14") (pinfunction "PH2(XCK2)_14") (pintype "bidirectional"))
    )
    (net (code "118") (name "unconnected-(IC3-PH7(T4)-Pad27)") (class "Default")
      (node (ref "IC3") (pin "27") (pinfunction "PH7(T4)_27") (pintype "bidirectional"))
    )
    (net (code "119") (name "unconnected-(IC3-PJ2(XCK3{slash}PCINT11)-Pad65)") (class "Default")
      (node (ref "IC3") (pin "65") (pinfunction "PJ2(XCK3/PCINT11)_65") (pintype "bidirectional"))
    )
    (net (code "120") (name "unconnected-(IC3-PJ3(PCINT12)-Pad66)") (class "Default")
      (node (ref "IC3") (pin "66") (pinfunction "PJ3(PCINT12)_66") (pintype "bidirectional"))
    )
    (net (code "121") (name "unconnected-(IC3-PJ4(PCINT13)-Pad67)") (class "Default")
      (node (ref "IC3") (pin "67") (pinfunction "PJ4(PCINT13)_67") (pintype "bidirectional"))
    )
    (net (code "122") (name "unconnected-(IC3-PJ5(PCINT14)-Pad68)") (class "Default")
      (node (ref "IC3") (pin "68") (pinfunction "PJ5(PCINT14)_68") (pintype "bidirectional"))
    )
    (net (code "123") (name "unconnected-(IC3-PJ6(PCINT15)-Pad69)") (class "Default")
      (node (ref "IC3") (pin "69") (pinfunction "PJ6(PCINT15)_69") (pintype "bidirectional"))
    )
    (net (code "124") (name "unconnected-(IC3-PJ7-Pad79)") (class "Default")
      (node (ref "IC3") (pin "79") (pinfunction "PJ7_79") (pintype "bidirectional"))
    )
    (net (code "125") (name "unconnected-(IC4-(AIN0{slash}INT1)PD1-Pad7)") (class "Default")
      (node (ref "IC4") (pin "7") (pinfunction "(AIN0/INT1)PD1_7") (pintype "bidirectional"))
    )
    (net (code "126") (name "unconnected-(IC4-(AIN2{slash}PCINT11)PC2-Pad5)") (class "Default")
      (node (ref "IC4") (pin "5") (pinfunction "(AIN2/PCINT11)PC2_5") (pintype "bidirectional"))
    )
    (net (code "127") (name "unconnected-(IC4-(INT4{slash}ICP1{slash}CLK0)PC7-Pad22)") (class "Default")
      (node (ref "IC4") (pin "22") (pinfunction "(INT4/ICP1/CLK0)PC7_22") (pintype "bidirectional"))
    )
    (net (code "128") (name "unconnected-(IC4-(OC0B{slash}INT0)PD0-Pad6)") (class "Default")
      (node (ref "IC4") (pin "6") (pinfunction "(OC0B/INT0)PD0_6") (pintype "bidirectional"))
    )
    (net (code "129") (name "unconnected-(IC4-(OC1A{slash}PCINT8)PC6-Pad23)") (class "Default")
      (node (ref "IC4") (pin "23") (pinfunction "(OC1A/PCINT8)PC6_23") (pintype "bidirectional"))
    )
    (net (code "130") (name "unconnected-(IC4-(PCINT5)PB5-Pad19)") (class "Default")
      (node (ref "IC4") (pin "19") (pinfunction "(PCINT5)PB5_19") (pintype "bidirectional"))
    )
    (net (code "131") (name "unconnected-(IC4-(PCINT6)PB6-Pad20)") (class "Default")
      (node (ref "IC4") (pin "20") (pinfunction "(PCINT6)PB6_20") (pintype "bidirectional"))
    )
    (net (code "132") (name "unconnected-(IC4-(PCINT7{slash}OC0A{slash}OC1C)PB7-Pad21)") (class "Default")
      (node (ref "IC4") (pin "21") (pinfunction "(PCINT7/OC0A/OC1C)PB7_21") (pintype "bidirectional"))
    )
    (net (code "133") (name "unconnected-(IC4-(PCINT9{slash}OC1B)PC5-Pad25)") (class "Default")
      (node (ref "IC4") (pin "25") (pinfunction "(PCINT9/OC1B)PC5_25") (pintype "bidirectional"))
    )
    (net (code "134") (name "unconnected-(IC4-(PCINT10)PC4-Pad26)") (class "Default")
      (node (ref "IC4") (pin "26") (pinfunction "(PCINT10)PC4_26") (pintype "bidirectional"))
    )
    (net (code "135") (name "unconnected-(IC4-(RTS{slash}AIN5{slash}INT6)PD6-Pad12)") (class "Default")
      (node (ref "IC4") (pin "12") (pinfunction "(RTS/AIN5/INT6)PD6_12") (pintype "bidirectional"))
    )
    (net (code "136") (name "unconnected-(IC4-(SS{slash}PCINT0)PB0-Pad14)") (class "Default")
      (node (ref "IC4") (pin "14") (pinfunction "(SS/PCINT0)PB0_14") (pintype "bidirectional"))
    )
    (net (code "137") (name "unconnected-(IC4-(T1{slash}PCINT4)PB4-Pad18)") (class "Default")
      (node (ref "IC4") (pin "18") (pinfunction "(T1/PCINT4)PB4_18") (pintype "bidirectional"))
    )
    (net (code "138") (name "unconnected-(IC5A-OUT-Pad1)") (class "Default")
      (node (ref "IC5") (pin "1") (pinfunction "OUT_1") (pintype "output"))
    )
    (net (code "139") (name "unconnected-(IC6-NC{slash}FB-Pad4)") (class "Default")
      (node (ref "IC6") (pin "4") (pinfunction "NC/FB_4") (pintype "passive"))
    )
    (net (code "140") (name "unconnected-(RN1D-1-Pad4)") (class "Default")
      (node (ref "RN1") (pin "4") (pinfunction "1_4") (pintype "passive"))
    )
    (net (code "141") (name "unconnected-(RN1D-2-Pad5)") (class "Default")
      (node (ref "RN1") (pin "5") (pinfunction "2_5") (pintype "passive"))
    )
    (net (code "142") (name "unconnected-(RN2B-1-Pad2)") (class "Default")
      (node (ref "RN2") (pin "2") (pinfunction "1_2") (pintype "passive"))
    )
    (net (code "143") (name "unconnected-(RN2B-2-Pad7)") (class "Default")
      (node (ref "RN2") (pin "7") (pinfunction "2_7") (pintype "passive"))
    )
    (net (code "144") (name "unconnected-(RN2C-1-Pad3)") (class "Default")
      (node (ref "RN2") (pin "3") (pinfunction "1_3") (pintype "passive"))
    )
    (net (code "145") (name "unconnected-(RN2C-2-Pad6)") (class "Default")
      (node (ref "RN2") (pin "6") (pinfunction "2_6") (pintype "passive"))
    )
    (net (code "146") (name "unconnected-(RN3-Pad1)") (class "Default")
      (node (ref "RN3") (pin "1") (pinfunction "1_1") (pintype "passive"))
    )
    (net (code "147") (name "unconnected-(RN3A-2-Pad8)") (class "Default")
      (node (ref "RN3") (pin "8") (pinfunction "2_8") (pintype "passive"))
    )
    (net (code "148") (name "unconnected-(RN3B-1-Pad2)") (class "Default")
      (node (ref "RN3") (pin "2") (pinfunction "1_2") (pintype "passive"))
    )
    (net (code "149") (name "unconnected-(RN3B-2-Pad7)") (class "Default")
      (node (ref "RN3") (pin "7") (pinfunction "2_7") (pintype "passive"))
    )
    (net (code "150") (name "unconnected-(RN5D-1-Pad4)") (class "Default")
      (node (ref "RN5") (pin "4") (pinfunction "1_4") (pintype "passive"))
    )
    (net (code "151") (name "unconnected-(RN5D-2-Pad5)") (class "Default")
      (node (ref "RN5") (pin "5") (pinfunction "2_5") (pintype "passive"))
    )
  )
)
